# LCD_Cape.net
KiCad netlist of a schematic drawn in Altium Designer
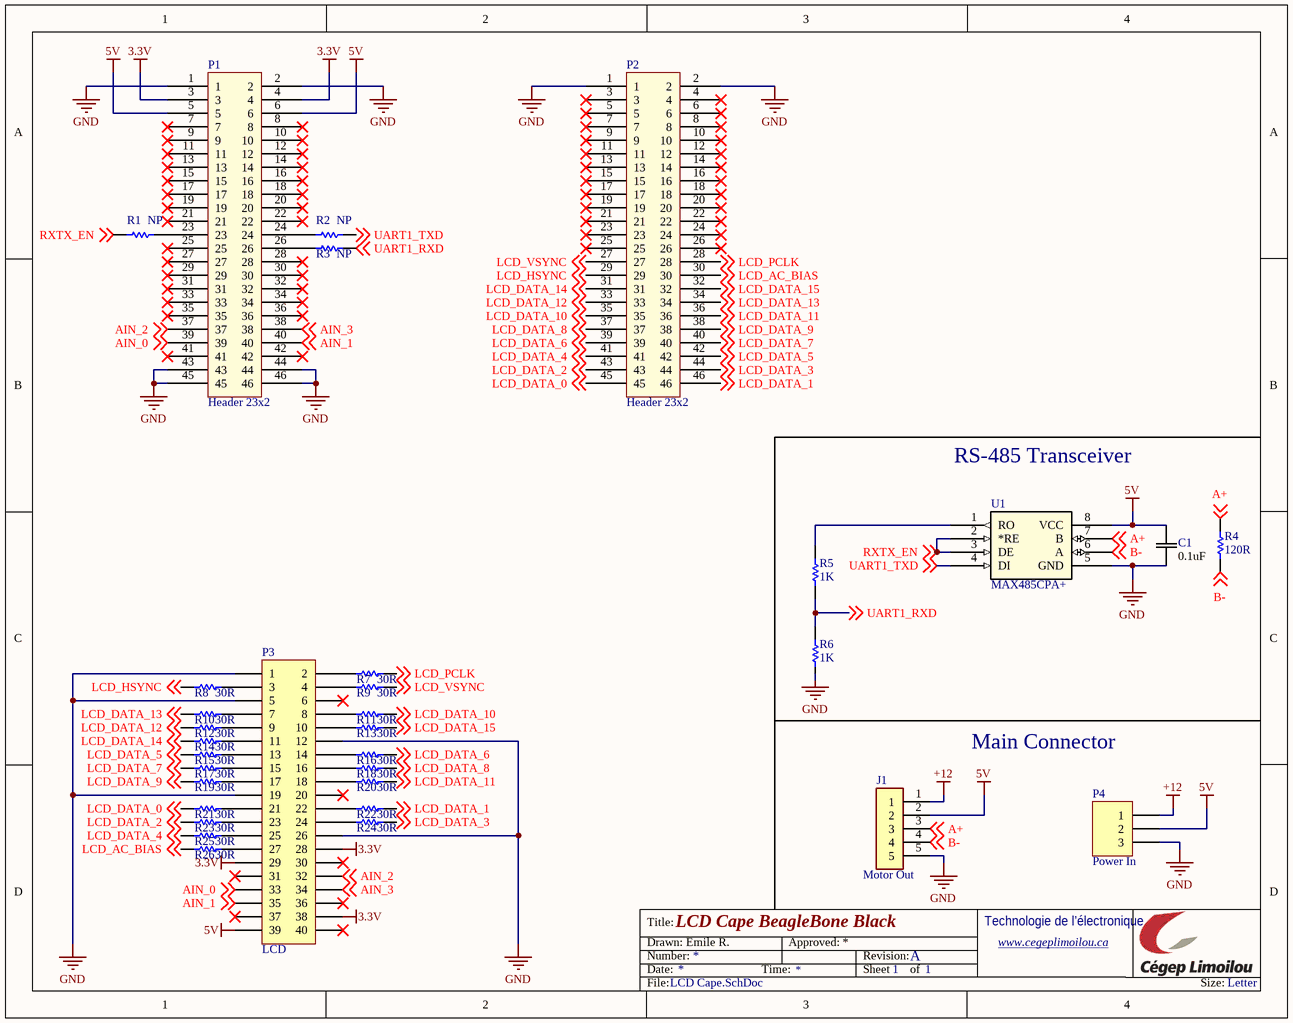
[diagram p0: LCD Cape.SchDoc]

(export (version "E")
  (design (tool "Eeschema 10.0.6"))
  (components
    (comp (ref "C1")
      (value "0.1uF")
      (footprint "0603")
      (description "Capacitor SMD 1206")
      (fields
        (field (name "MANUFACTURER_PART_NUMBER") "12065A820JAT2A")
        (field (name "Comment") "Capacitor 1206")
        (field (name "COPYRIGHT") "Copyright (C) 2018 Accelerated Designs. All rights reserved")
      )
      (libsource (lib "Schematic_Emile") (part "Capacitor 1206"))
    )
    (comp (ref "J1")
      (value "Motor Out")
      (footprint "JST 5POS 2.5mm 90°")
      (description "Connector")
      (fields (field (name "MANUFACTURER_PART_NUMBER") "S5B-XH-A-1(LF)(SN)"))
      (libsource (lib "Schematic_Emile") (part "JST 5POS"))
    )
    (comp (ref "P1")
      (value "Header 23x2")
      (footprint "Header 23x2")
      (libsource (lib "Schematic_Emile") (part "Header 23x2"))
    )
    (comp (ref "P2")
      (value "Header 23x2")
      (footprint "Header 23x2")
      (libsource (lib "Schematic_Emile") (part "Header 23x2"))
    )
    (comp (ref "P3")
      (value "LCD")
      (footprint "HDR2X20")
      (description "Header, 20-Pin, Dual row")
      (fields (field (name "PUBLISHER") "Altium Limited"))
      (libsource (lib "Miscellaneous Connectors") (part "Header 20X2"))
    )
    (comp (ref "P4")
      (value "Power In")
      (footprint "HDR1X3")
      (description "Header, 3-Pin")
      (fields (field (name "PUBLISHER") "Altium Limited"))
      (libsource (lib "Miscellaneous Connectors") (part "Header 3"))
    )
    (comp (ref "R1")
      (value "NP")
      (footprint "C1206")
      (description "Resistor")
      (fields (field (name "Comment") "Res1") (field (name "PUBLISHER") "Altium Limited"))
      (libsource (lib "Miscellaneous Devices") (part "Res1"))
    )
    (comp (ref "R2")
      (value "NP")
      (footprint "C1206")
      (description "Resistor")
      (fields (field (name "Comment") "Res1") (field (name "PUBLISHER") "Altium Limited"))
      (libsource (lib "Miscellaneous Devices") (part "Res1"))
    )
    (comp (ref "R3")
      (value "NP")
      (footprint "C1206")
      (description "Resistor")
      (fields (field (name "Comment") "Res1") (field (name "PUBLISHER") "Altium Limited"))
      (libsource (lib "Miscellaneous Devices") (part "Res1"))
    )
    (comp (ref "R4")
      (value "120R")
      (footprint "C1206")
      (description "Resistor")
      (fields (field (name "Comment") "Res1") (field (name "PUBLISHER") "Altium Limited"))
      (libsource (lib "Miscellaneous Devices") (part "Res1"))
    )
    (comp (ref "R5")
      (value "1K")
      (footprint "C1206")
      (description "Resistor")
      (fields (field (name "Comment") "Res1") (field (name "PUBLISHER") "Altium Limited"))
      (libsource (lib "Miscellaneous Devices") (part "Res1"))
    )
    (comp (ref "R6")
      (value "1K")
      (footprint "C1206")
      (description "Resistor")
      (fields (field (name "Comment") "Res1") (field (name "PUBLISHER") "Altium Limited"))
      (libsource (lib "Miscellaneous Devices") (part "Res1"))
    )
    (comp (ref "R7")
      (value "30R")
      (footprint "C1206")
      (description "Resistor")
      (fields (field (name "Comment") "Res1") (field (name "PUBLISHER") "Altium Limited"))
      (libsource (lib "Miscellaneous Devices") (part "Res1"))
    )
    (comp (ref "R8")
      (value "30R")
      (footprint "C1206")
      (description "Resistor")
      (fields (field (name "Comment") "Res1") (field (name "PUBLISHER") "Altium Limited"))
      (libsource (lib "Miscellaneous Devices") (part "Res1"))
    )
    (comp (ref "R9")
      (value "30R")
      (footprint "C1206")
      (description "Resistor")
      (fields (field (name "Comment") "Res1") (field (name "PUBLISHER") "Altium Limited"))
      (libsource (lib "Miscellaneous Devices") (part "Res1"))
    )
    (comp (ref "R10")
      (value "30R")
      (footprint "C1206")
      (description "Resistor")
      (fields (field (name "Comment") "Res1") (field (name "PUBLISHER") "Altium Limited"))
      (libsource (lib "Miscellaneous Devices") (part "Res1"))
    )
    (comp (ref "R11")
      (value "30R")
      (footprint "C1206")
      (description "Resistor")
      (fields (field (name "Comment") "Res1") (field (name "PUBLISHER") "Altium Limited"))
      (libsource (lib "Miscellaneous Devices") (part "Res1"))
    )
    (comp (ref "R12")
      (value "30R")
      (footprint "C1206")
      (description "Resistor")
      (fields (field (name "Comment") "Res1") (field (name "PUBLISHER") "Altium Limited"))
      (libsource (lib "Miscellaneous Devices") (part "Res1"))
    )
    (comp (ref "R13")
      (value "30R")
      (footprint "C1206")
      (description "Resistor")
      (fields (field (name "Comment") "Res1") (field (name "PUBLISHER") "Altium Limited"))
      (libsource (lib "Miscellaneous Devices") (part "Res1"))
    )
    (comp (ref "R14")
      (value "30R")
      (footprint "C1206")
      (description "Resistor")
      (fields (field (name "Comment") "Res1") (field (name "PUBLISHER") "Altium Limited"))
      (libsource (lib "Miscellaneous Devices") (part "Res1"))
    )
    (comp (ref "R15")
      (value "30R")
      (footprint "C1206")
      (description "Resistor")
      (fields (field (name "Comment") "Res1") (field (name "PUBLISHER") "Altium Limited"))
      (libsource (lib "Miscellaneous Devices") (part "Res1"))
    )
    (comp (ref "R16")
      (value "30R")
      (footprint "C1206")
      (description "Resistor")
      (fields (field (name "Comment") "Res1") (field (name "PUBLISHER") "Altium Limited"))
      (libsource (lib "Miscellaneous Devices") (part "Res1"))
    )
    (comp (ref "R17")
      (value "30R")
      (footprint "C1206")
      (description "Resistor")
      (fields (field (name "Comment") "Res1") (field (name "PUBLISHER") "Altium Limited"))
      (libsource (lib "Miscellaneous Devices") (part "Res1"))
    )
    (comp (ref "R18")
      (value "30R")
      (footprint "C1206")
      (description "Resistor")
      (fields (field (name "Comment") "Res1") (field (name "PUBLISHER") "Altium Limited"))
      (libsource (lib "Miscellaneous Devices") (part "Res1"))
    )
    (comp (ref "R19")
      (value "30R")
      (footprint "C1206")
      (description "Resistor")
      (fields (field (name "Comment") "Res1") (field (name "PUBLISHER") "Altium Limited"))
      (libsource (lib "Miscellaneous Devices") (part "Res1"))
    )
    (comp (ref "R20")
      (value "30R")
      (footprint "C1206")
      (description "Resistor")
      (fields (field (name "Comment") "Res1") (field (name "PUBLISHER") "Altium Limited"))
      (libsource (lib "Miscellaneous Devices") (part "Res1"))
    )
    (comp (ref "R21")
      (value "30R")
      (footprint "C1206")
      (description "Resistor")
      (fields (field (name "Comment") "Res1") (field (name "PUBLISHER") "Altium Limited"))
      (libsource (lib "Miscellaneous Devices") (part "Res1"))
    )
    (comp (ref "R22")
      (value "30R")
      (footprint "C1206")
      (description "Resistor")
      (fields (field (name "Comment") "Res1") (field (name "PUBLISHER") "Altium Limited"))
      (libsource (lib "Miscellaneous Devices") (part "Res1"))
    )
    (comp (ref "R23")
      (value "30R")
      (footprint "C1206")
      (description "Resistor")
      (fields (field (name "Comment") "Res1") (field (name "PUBLISHER") "Altium Limited"))
      (libsource (lib "Miscellaneous Devices") (part "Res1"))
    )
    (comp (ref "R24")
      (value "30R")
      (footprint "C1206")
      (description "Resistor")
      (fields (field (name "Comment") "Res1") (field (name "PUBLISHER") "Altium Limited"))
      (libsource (lib "Miscellaneous Devices") (part "Res1"))
    )
    (comp (ref "R25")
      (value "30R")
      (footprint "C1206")
      (description "Resistor")
      (fields (field (name "Comment") "Res1") (field (name "PUBLISHER") "Altium Limited"))
      (libsource (lib "Miscellaneous Devices") (part "Res1"))
    )
    (comp (ref "R26")
      (value "30R")
      (footprint "C1206")
      (description "Resistor")
      (fields (field (name "Comment") "Res1") (field (name "PUBLISHER") "Altium Limited"))
      (libsource (lib "Miscellaneous Devices") (part "Res1"))
    )
    (comp (ref "U1")
      (value "MAX485CPA+")
      (footprint "DIP 8 - 3D")
      (description "RS485 Communication")
      (fields (field (name "COPYRIGHT") "Copyright (C) 2018 Accelerated Designs. All rights reserved"))
      (libsource (lib "Schematic_Emile") (part "MAX485CPA+"))
    )
  )
  (nets
    (net (code "1") (name "+12") (class "Default")
      (node (ref "J1") (pin "1") (pinfunction "1_1") (pintype "passive"))
      (node (ref "P4") (pin "1") (pinfunction "1_1") (pintype "passive"))
    )
    (net (code "2") (name "3.3V") (class "Default")
      (node (ref "P1") (pin "3") (pinfunction "3_3") (pintype "passive"))
      (node (ref "P1") (pin "4") (pinfunction "4_4") (pintype "passive"))
      (node (ref "P3") (pin "28") (pinfunction "28_28") (pintype "passive"))
      (node (ref "P3") (pin "29") (pinfunction "29_29") (pintype "passive"))
      (node (ref "P3") (pin "38") (pinfunction "38_38") (pintype "passive"))
    )
    (net (code "3") (name "5V") (class "Default")
      (node (ref "C1") (pin "2") (pinfunction "2_2") (pintype "passive"))
      (node (ref "J1") (pin "2") (pinfunction "2_2") (pintype "passive"))
      (node (ref "P1") (pin "5") (pinfunction "5_5") (pintype "passive"))
      (node (ref "P1") (pin "6") (pinfunction "6_6") (pintype "passive"))
      (node (ref "P3") (pin "39") (pinfunction "39_39") (pintype "passive"))
      (node (ref "P4") (pin "2") (pinfunction "2_2") (pintype "passive"))
      (node (ref "U1") (pin "8") (pinfunction "VCC_8") (pintype "power_in"))
    )
    (net (code "4") (name "A+") (class "Default")
      (node (ref "J1") (pin "3") (pinfunction "3_3") (pintype "passive"))
      (node (ref "R4") (pin "1") (pinfunction "1_1") (pintype "passive"))
      (node (ref "U1") (pin "7") (pinfunction "B_7") (pintype "bidirectional"))
    )
    (net (code "5") (name "AIN_0") (class "Default")
      (node (ref "P1") (pin "39") (pinfunction "39_39") (pintype "passive"))
      (node (ref "P3") (pin "33") (pinfunction "33_33") (pintype "passive"))
    )
    (net (code "6") (name "AIN_1") (class "Default")
      (node (ref "P1") (pin "40") (pinfunction "40_40") (pintype "passive"))
      (node (ref "P3") (pin "35") (pinfunction "35_35") (pintype "passive"))
    )
    (net (code "7") (name "AIN_2") (class "Default")
      (node (ref "P1") (pin "37") (pinfunction "37_37") (pintype "passive"))
      (node (ref "P3") (pin "32") (pinfunction "32_32") (pintype "passive"))
    )
    (net (code "8") (name "AIN_3") (class "Default")
      (node (ref "P1") (pin "38") (pinfunction "38_38") (pintype "passive"))
      (node (ref "P3") (pin "34") (pinfunction "34_34") (pintype "passive"))
    )
    (net (code "9") (name "B-") (class "Default")
      (node (ref "J1") (pin "4") (pinfunction "4_4") (pintype "passive"))
      (node (ref "R4") (pin "2") (pinfunction "2_2") (pintype "passive"))
      (node (ref "U1") (pin "6") (pinfunction "A_6") (pintype "bidirectional"))
    )
    (net (code "10") (name "GND") (class "Default")
      (node (ref "C1") (pin "1") (pinfunction "1_1") (pintype "passive"))
      (node (ref "J1") (pin "5") (pinfunction "5_5") (pintype "passive"))
      (node (ref "P1") (pin "1") (pinfunction "1_1") (pintype "passive"))
      (node (ref "P1") (pin "2") (pinfunction "2_2") (pintype "passive"))
      (node (ref "P1") (pin "43") (pinfunction "43_43") (pintype "passive"))
      (node (ref "P1") (pin "44") (pinfunction "44_44") (pintype "passive"))
      (node (ref "P1") (pin "45") (pinfunction "45_45") (pintype "passive"))
      (node (ref "P1") (pin "46") (pinfunction "46_46") (pintype "passive"))
      (node (ref "P2") (pin "1") (pinfunction "1_1") (pintype "passive"))
      (node (ref "P2") (pin "2") (pinfunction "2_2") (pintype "passive"))
      (node (ref "P3") (pin "1") (pinfunction "1_1") (pintype "passive"))
      (node (ref "P3") (pin "12") (pinfunction "12_12") (pintype "passive"))
      (node (ref "P3") (pin "19") (pinfunction "19_19") (pintype "passive"))
      (node (ref "P3") (pin "26") (pinfunction "26_26") (pintype "passive"))
      (node (ref "P3") (pin "5") (pinfunction "5_5") (pintype "passive"))
      (node (ref "P4") (pin "3") (pinfunction "3_3") (pintype "passive"))
      (node (ref "R6") (pin "2") (pinfunction "2_2") (pintype "passive"))
      (node (ref "U1") (pin "5") (pinfunction "GND_5") (pintype "power_in"))
    )
    (net (code "11") (name "LCD_AC_BIAS") (class "Default")
      (node (ref "P2") (pin "30") (pinfunction "30_30") (pintype "passive"))
      (node (ref "R26") (pin "1") (pinfunction "1_1") (pintype "passive"))
    )
    (net (code "12") (name "LCD_DATA_0") (class "Default")
      (node (ref "P2") (pin "45") (pinfunction "45_45") (pintype "passive"))
      (node (ref "R21") (pin "1") (pinfunction "1_1") (pintype "passive"))
    )
    (net (code "13") (name "LCD_DATA_1") (class "Default")
      (node (ref "P2") (pin "46") (pinfunction "46_46") (pintype "passive"))
      (node (ref "R22") (pin "2") (pinfunction "2_2") (pintype "passive"))
    )
    (net (code "14") (name "LCD_DATA_2") (class "Default")
      (node (ref "P2") (pin "43") (pinfunction "43_43") (pintype "passive"))
      (node (ref "R23") (pin "1") (pinfunction "1_1") (pintype "passive"))
    )
    (net (code "15") (name "LCD_DATA_3") (class "Default")
      (node (ref "P2") (pin "44") (pinfunction "44_44") (pintype "passive"))
      (node (ref "R24") (pin "2") (pinfunction "2_2") (pintype "passive"))
    )
    (net (code "16") (name "LCD_DATA_4") (class "Default")
      (node (ref "P2") (pin "41") (pinfunction "41_41") (pintype "passive"))
      (node (ref "R25") (pin "1") (pinfunction "1_1") (pintype "passive"))
    )
    (net (code "17") (name "LCD_DATA_5") (class "Default")
      (node (ref "P2") (pin "42") (pinfunction "42_42") (pintype "passive"))
      (node (ref "R15") (pin "1") (pinfunction "1_1") (pintype "passive"))
    )
    (net (code "18") (name "LCD_DATA_6") (class "Default")
      (node (ref "P2") (pin "39") (pinfunction "39_39") (pintype "passive"))
      (node (ref "R16") (pin "2") (pinfunction "2_2") (pintype "passive"))
    )
    (net (code "19") (name "LCD_DATA_7") (class "Default")
      (node (ref "P2") (pin "40") (pinfunction "40_40") (pintype "passive"))
      (node (ref "R17") (pin "1") (pinfunction "1_1") (pintype "passive"))
    )
    (net (code "20") (name "LCD_DATA_8") (class "Default")
      (node (ref "P2") (pin "37") (pinfunction "37_37") (pintype "passive"))
      (node (ref "R18") (pin "2") (pinfunction "2_2") (pintype "passive"))
    )
    (net (code "21") (name "LCD_DATA_9") (class "Default")
      (node (ref "P2") (pin "38") (pinfunction "38_38") (pintype "passive"))
      (node (ref "R19") (pin "1") (pinfunction "1_1") (pintype "passive"))
    )
    (net (code "22") (name "LCD_DATA_10") (class "Default")
      (node (ref "P2") (pin "35") (pinfunction "35_35") (pintype "passive"))
      (node (ref "R11") (pin "2") (pinfunction "2_2") (pintype "passive"))
    )
    (net (code "23") (name "LCD_DATA_11") (class "Default")
      (node (ref "P2") (pin "36") (pinfunction "36_36") (pintype "passive"))
      (node (ref "R20") (pin "2") (pinfunction "2_2") (pintype "passive"))
    )
    (net (code "24") (name "LCD_DATA_12") (class "Default")
      (node (ref "P2") (pin "33") (pinfunction "33_33") (pintype "passive"))
      (node (ref "R12") (pin "1") (pinfunction "1_1") (pintype "passive"))
    )
    (net (code "25") (name "LCD_DATA_13") (class "Default")
      (node (ref "P2") (pin "34") (pinfunction "34_34") (pintype "passive"))
      (node (ref "R10") (pin "1") (pinfunction "1_1") (pintype "passive"))
    )
    (net (code "26") (name "LCD_DATA_14") (class "Default")
      (node (ref "P2") (pin "31") (pinfunction "31_31") (pintype "passive"))
      (node (ref "R14") (pin "1") (pinfunction "1_1") (pintype "passive"))
    )
    (net (code "27") (name "LCD_DATA_15") (class "Default")
      (node (ref "P2") (pin "32") (pinfunction "32_32") (pintype "passive"))
      (node (ref "R13") (pin "2") (pinfunction "2_2") (pintype "passive"))
    )
    (net (code "28") (name "LCD_HSYNC") (class "Default")
      (node (ref "P2") (pin "29") (pinfunction "29_29") (pintype "passive"))
      (node (ref "R8") (pin "1") (pinfunction "1_1") (pintype "passive"))
    )
    (net (code "29") (name "LCD_PCLK") (class "Default")
      (node (ref "P2") (pin "28") (pinfunction "28_28") (pintype "passive"))
      (node (ref "R7") (pin "2") (pinfunction "2_2") (pintype "passive"))
    )
    (net (code "30") (name "LCD_VSYNC") (class "Default")
      (node (ref "P2") (pin "27") (pinfunction "27_27") (pintype "passive"))
      (node (ref "R9") (pin "2") (pinfunction "2_2") (pintype "passive"))
    )
    (net (code "31") (name "Net-(P1-Pad23)") (class "Default")
      (node (ref "P1") (pin "23") (pinfunction "23_23") (pintype "passive"))
      (node (ref "R1") (pin "2") (pinfunction "2_2") (pintype "passive"))
    )
    (net (code "32") (name "Net-(P1-Pad24)") (class "Default")
      (node (ref "P1") (pin "24") (pinfunction "24_24") (pintype "passive"))
      (node (ref "R2") (pin "1") (pinfunction "1_1") (pintype "passive"))
    )
    (net (code "33") (name "Net-(P1-Pad26)") (class "Default")
      (node (ref "P1") (pin "26") (pinfunction "26_26") (pintype "passive"))
      (node (ref "R3") (pin "1") (pinfunction "1_1") (pintype "passive"))
    )
    (net (code "34") (name "Net-(P3-Pad2)") (class "Default")
      (node (ref "P3") (pin "2") (pinfunction "2_2") (pintype "passive"))
      (node (ref "R7") (pin "1") (pinfunction "1_1") (pintype "passive"))
    )
    (net (code "35") (name "Net-(P3-Pad3)") (class "Default")
      (node (ref "P3") (pin "3") (pinfunction "3_3") (pintype "passive"))
      (node (ref "R8") (pin "2") (pinfunction "2_2") (pintype "passive"))
    )
    (net (code "36") (name "Net-(P3-Pad4)") (class "Default")
      (node (ref "P3") (pin "4") (pinfunction "4_4") (pintype "passive"))
      (node (ref "R9") (pin "1") (pinfunction "1_1") (pintype "passive"))
    )
    (net (code "37") (name "Net-(P3-Pad7)") (class "Default")
      (node (ref "P3") (pin "7") (pinfunction "7_7") (pintype "passive"))
      (node (ref "R10") (pin "2") (pinfunction "2_2") (pintype "passive"))
    )
    (net (code "38") (name "Net-(P3-Pad8)") (class "Default")
      (node (ref "P3") (pin "8") (pinfunction "8_8") (pintype "passive"))
      (node (ref "R11") (pin "1") (pinfunction "1_1") (pintype "passive"))
    )
    (net (code "39") (name "Net-(P3-Pad9)") (class "Default")
      (node (ref "P3") (pin "9") (pinfunction "9_9") (pintype "passive"))
      (node (ref "R12") (pin "2") (pinfunction "2_2") (pintype "passive"))
    )
    (net (code "40") (name "Net-(P3-Pad10)") (class "Default")
      (node (ref "P3") (pin "10") (pinfunction "10_10") (pintype "passive"))
      (node (ref "R13") (pin "1") (pinfunction "1_1") (pintype "passive"))
    )
    (net (code "41") (name "Net-(P3-Pad11)") (class "Default")
      (node (ref "P3") (pin "11") (pinfunction "11_11") (pintype "passive"))
      (node (ref "R14") (pin "2") (pinfunction "2_2") (pintype "passive"))
    )
    (net (code "42") (name "Net-(P3-Pad13)") (class "Default")
      (node (ref "P3") (pin "13") (pinfunction "13_13") (pintype "passive"))
      (node (ref "R15") (pin "2") (pinfunction "2_2") (pintype "passive"))
    )
    (net (code "43") (name "Net-(P3-Pad14)") (class "Default")
      (node (ref "P3") (pin "14") (pinfunction "14_14") (pintype "passive"))
      (node (ref "R16") (pin "1") (pinfunction "1_1") (pintype "passive"))
    )
    (net (code "44") (name "Net-(P3-Pad15)") (class "Default")
      (node (ref "P3") (pin "15") (pinfunction "15_15") (pintype "passive"))
      (node (ref "R17") (pin "2") (pinfunction "2_2") (pintype "passive"))
    )
    (net (code "45") (name "Net-(P3-Pad16)") (class "Default")
      (node (ref "P3") (pin "16") (pinfunction "16_16") (pintype "passive"))
      (node (ref "R18") (pin "1") (pinfunction "1_1") (pintype "passive"))
    )
    (net (code "46") (name "Net-(P3-Pad17)") (class "Default")
      (node (ref "P3") (pin "17") (pinfunction "17_17") (pintype "passive"))
      (node (ref "R19") (pin "2") (pinfunction "2_2") (pintype "passive"))
    )
    (net (code "47") (name "Net-(P3-Pad18)") (class "Default")
      (node (ref "P3") (pin "18") (pinfunction "18_18") (pintype "passive"))
      (node (ref "R20") (pin "1") (pinfunction "1_1") (pintype "passive"))
    )
    (net (code "48") (name "Net-(P3-Pad21)") (class "Default")
      (node (ref "P3") (pin "21") (pinfunction "21_21") (pintype "passive"))
      (node (ref "R21") (pin "2") (pinfunction "2_2") (pintype "passive"))
    )
    (net (code "49") (name "Net-(P3-Pad22)") (class "Default")
      (node (ref "P3") (pin "22") (pinfunction "22_22") (pintype "passive"))
      (node (ref "R22") (pin "1") (pinfunction "1_1") (pintype "passive"))
    )
    (net (code "50") (name "Net-(P3-Pad23)") (class "Default")
      (node (ref "P3") (pin "23") (pinfunction "23_23") (pintype "passive"))
      (node (ref "R23") (pin "2") (pinfunction "2_2") (pintype "passive"))
    )
    (net (code "51") (name "Net-(P3-Pad24)") (class "Default")
      (node (ref "P3") (pin "24") (pinfunction "24_24") (pintype "passive"))
      (node (ref "R24") (pin "1") (pinfunction "1_1") (pintype "passive"))
    )
    (net (code "52") (name "Net-(P3-Pad25)") (class "Default")
      (node (ref "P3") (pin "25") (pinfunction "25_25") (pintype "passive"))
      (node (ref "R25") (pin "2") (pinfunction "2_2") (pintype "passive"))
    )
    (net (code "53") (name "Net-(P3-Pad27)") (class "Default")
      (node (ref "P3") (pin "27") (pinfunction "27_27") (pintype "passive"))
      (node (ref "R26") (pin "2") (pinfunction "2_2") (pintype "passive"))
    )
    (net (code "54") (name "Net-(U1-RO)") (class "Default")
      (node (ref "R5") (pin "1") (pinfunction "1_1") (pintype "passive"))
      (node (ref "U1") (pin "1") (pinfunction "RO_1") (pintype "output"))
    )
    (net (code "55") (name "RXTX_EN") (class "Default")
      (node (ref "R1") (pin "1") (pinfunction "1_1") (pintype "passive"))
      (node (ref "U1") (pin "2") (pinfunction "*RE_2") (pintype "input"))
      (node (ref "U1") (pin "3") (pinfunction "DE_3") (pintype "input"))
    )
    (net (code "56") (name "UART1_RXD") (class "Default")
      (node (ref "R3") (pin "2") (pinfunction "2_2") (pintype "passive"))
      (node (ref "R5") (pin "2") (pinfunction "2_2") (pintype "passive"))
      (node (ref "R6") (pin "1") (pinfunction "1_1") (pintype "passive"))
    )
    (net (code "57") (name "UART1_TXD") (class "Default")
      (node (ref "R2") (pin "2") (pinfunction "2_2") (pintype "passive"))
      (node (ref "U1") (pin "4") (pinfunction "DI_4") (pintype "input"))
    )
    (net (code "58") (name "unconnected-(P1-Pad7)") (class "Default")
      (node (ref "P1") (pin "7") (pinfunction "7_7") (pintype "passive+no_connect"))
    )
    (net (code "59") (name "unconnected-(P1-Pad8)") (class "Default")
      (node (ref "P1") (pin "8") (pinfunction "8_8") (pintype "passive+no_connect"))
    )
    (net (code "60") (name "unconnected-(P1-Pad9)") (class "Default")
      (node (ref "P1") (pin "9") (pinfunction "9_9") (pintype "passive+no_connect"))
    )
    (net (code "61") (name "unconnected-(P1-Pad10)") (class "Default")
      (node (ref "P1") (pin "10") (pinfunction "10_10") (pintype "passive+no_connect"))
    )
    (net (code "62") (name "unconnected-(P1-Pad11)") (class "Default")
      (node (ref "P1") (pin "11") (pinfunction "11_11") (pintype "passive+no_connect"))
    )
    (net (code "63") (name "unconnected-(P1-Pad12)") (class "Default")
      (node (ref "P1") (pin "12") (pinfunction "12_12") (pintype "passive+no_connect"))
    )
    (net (code "64") (name "unconnected-(P1-Pad13)") (class "Default")
      (node (ref "P1") (pin "13") (pinfunction "13_13") (pintype "passive+no_connect"))
    )
    (net (code "65") (name "unconnected-(P1-Pad14)") (class "Default")
      (node (ref "P1") (pin "14") (pinfunction "14_14") (pintype "passive+no_connect"))
    )
    (net (code "66") (name "unconnected-(P1-Pad15)") (class "Default")
      (node (ref "P1") (pin "15") (pinfunction "15_15") (pintype "passive+no_connect"))
    )
    (net (code "67") (name "unconnected-(P1-Pad16)") (class "Default")
      (node (ref "P1") (pin "16") (pinfunction "16_16") (pintype "passive+no_connect"))
    )
    (net (code "68") (name "unconnected-(P1-Pad17)") (class "Default")
      (node (ref "P1") (pin "17") (pinfunction "17_17") (pintype "passive+no_connect"))
    )
    (net (code "69") (name "unconnected-(P1-Pad18)") (class "Default")
      (node (ref "P1") (pin "18") (pinfunction "18_18") (pintype "passive+no_connect"))
    )
    (net (code "70") (name "unconnected-(P1-Pad19)") (class "Default")
      (node (ref "P1") (pin "19") (pinfunction "19_19") (pintype "passive+no_connect"))
    )
    (net (code "71") (name "unconnected-(P1-Pad20)") (class "Default")
      (node (ref "P1") (pin "20") (pinfunction "20_20") (pintype "passive+no_connect"))
    )
    (net (code "72") (name "unconnected-(P1-Pad21)") (class "Default")
      (node (ref "P1") (pin "21") (pinfunction "21_21") (pintype "passive+no_connect"))
    )
    (net (code "73") (name "unconnected-(P1-Pad22)") (class "Default")
      (node (ref "P1") (pin "22") (pinfunction "22_22") (pintype "passive+no_connect"))
    )
    (net (code "74") (name "unconnected-(P1-Pad25)") (class "Default")
      (node (ref "P1") (pin "25") (pinfunction "25_25") (pintype "passive+no_connect"))
    )
    (net (code "75") (name "unconnected-(P1-Pad27)") (class "Default")
      (node (ref "P1") (pin "27") (pinfunction "27_27") (pintype "passive+no_connect"))
    )
    (net (code "76") (name "unconnected-(P1-Pad28)") (class "Default")
      (node (ref "P1") (pin "28") (pinfunction "28_28") (pintype "passive+no_connect"))
    )
    (net (code "77") (name "unconnected-(P1-Pad29)") (class "Default")
      (node (ref "P1") (pin "29") (pinfunction "29_29") (pintype "passive+no_connect"))
    )
    (net (code "78") (name "unconnected-(P1-Pad30)") (class "Default")
      (node (ref "P1") (pin "30") (pinfunction "30_30") (pintype "passive+no_connect"))
    )
    (net (code "79") (name "unconnected-(P1-Pad31)") (class "Default")
      (node (ref "P1") (pin "31") (pinfunction "31_31") (pintype "passive+no_connect"))
    )
    (net (code "80") (name "unconnected-(P1-Pad32)") (class "Default")
      (node (ref "P1") (pin "32") (pinfunction "32_32") (pintype "passive+no_connect"))
    )
    (net (code "81") (name "unconnected-(P1-Pad33)") (class "Default")
      (node (ref "P1") (pin "33") (pinfunction "33_33") (pintype "passive+no_connect"))
    )
    (net (code "82") (name "unconnected-(P1-Pad34)") (class "Default")
      (node (ref "P1") (pin "34") (pinfunction "34_34") (pintype "passive+no_connect"))
    )
    (net (code "83") (name "unconnected-(P1-Pad35)") (class "Default")
      (node (ref "P1") (pin "35") (pinfunction "35_35") (pintype "passive+no_connect"))
    )
    (net (code "84") (name "unconnected-(P1-Pad36)") (class "Default")
      (node (ref "P1") (pin "36") (pinfunction "36_36") (pintype "passive+no_connect"))
    )
    (net (code "85") (name "unconnected-(P1-Pad41)") (class "Default")
      (node (ref "P1") (pin "41") (pinfunction "41_41") (pintype "passive+no_connect"))
    )
    (net (code "86") (name "unconnected-(P1-Pad42)") (class "Default")
      (node (ref "P1") (pin "42") (pinfunction "42_42") (pintype "passive+no_connect"))
    )
    (net (code "87") (name "unconnected-(P2-Pad3)") (class "Default")
      (node (ref "P2") (pin "3") (pinfunction "3_3") (pintype "passive+no_connect"))
    )
    (net (code "88") (name "unconnected-(P2-Pad4)") (class "Default")
      (node (ref "P2") (pin "4") (pinfunction "4_4") (pintype "passive+no_connect"))
    )
    (net (code "89") (name "unconnected-(P2-Pad5)") (class "Default")
      (node (ref "P2") (pin "5") (pinfunction "5_5") (pintype "passive+no_connect"))
    )
    (net (code "90") (name "unconnected-(P2-Pad6)") (class "Default")
      (node (ref "P2") (pin "6") (pinfunction "6_6") (pintype "passive+no_connect"))
    )
    (net (code "91") (name "unconnected-(P2-Pad7)") (class "Default")
      (node (ref "P2") (pin "7") (pinfunction "7_7") (pintype "passive+no_connect"))
    )
    (net (code "92") (name "unconnected-(P2-Pad8)") (class "Default")
      (node (ref "P2") (pin "8") (pinfunction "8_8") (pintype "passive+no_connect"))
    )
    (net (code "93") (name "unconnected-(P2-Pad9)") (class "Default")
      (node (ref "P2") (pin "9") (pinfunction "9_9") (pintype "passive+no_connect"))
    )
    (net (code "94") (name "unconnected-(P2-Pad10)") (class "Default")
      (node (ref "P2") (pin "10") (pinfunction "10_10") (pintype "passive+no_connect"))
    )
    (net (code "95") (name "unconnected-(P2-Pad11)") (class "Default")
      (node (ref "P2") (pin "11") (pinfunction "11_11") (pintype "passive+no_connect"))
    )
    (net (code "96") (name "unconnected-(P2-Pad12)") (class "Default")
      (node (ref "P2") (pin "12") (pinfunction "12_12") (pintype "passive+no_connect"))
    )
    (net (code "97") (name "unconnected-(P2-Pad13)") (class "Default")
      (node (ref "P2") (pin "13") (pinfunction "13_13") (pintype "passive+no_connect"))
    )
    (net (code "98") (name "unconnected-(P2-Pad14)") (class "Default")
      (node (ref "P2") (pin "14") (pinfunction "14_14") (pintype "passive+no_connect"))
    )
    (net (code "99") (name "unconnected-(P2-Pad15)") (class "Default")
      (node (ref "P2") (pin "15") (pinfunction "15_15") (pintype "passive+no_connect"))
    )
    (net (code "100") (name "unconnected-(P2-Pad16)") (class "Default")
      (node (ref "P2") (pin "16") (pinfunction "16_16") (pintype "passive+no_connect"))
    )
    (net (code "101") (name "unconnected-(P2-Pad17)") (class "Default")
      (node (ref "P2") (pin "17") (pinfunction "17_17") (pintype "passive+no_connect"))
    )
    (net (code "102") (name "unconnected-(P2-Pad18)") (class "Default")
      (node (ref "P2") (pin "18") (pinfunction "18_18") (pintype "passive+no_connect"))
    )
    (net (code "103") (name "unconnected-(P2-Pad19)") (class "Default")
      (node (ref "P2") (pin "19") (pinfunction "19_19") (pintype "passive+no_connect"))
    )
    (net (code "104") (name "unconnected-(P2-Pad20)") (class "Default")
      (node (ref "P2") (pin "20") (pinfunction "20_20") (pintype "passive+no_connect"))
    )
    (net (code "105") (name "unconnected-(P2-Pad21)") (class "Default")
      (node (ref "P2") (pin "21") (pinfunction "21_21") (pintype "passive+no_connect"))
    )
    (net (code "106") (name "unconnected-(P2-Pad22)") (class "Default")
      (node (ref "P2") (pin "22") (pinfunction "22_22") (pintype "passive+no_connect"))
    )
    (net (code "107") (name "unconnected-(P2-Pad23)") (class "Default")
      (node (ref "P2") (pin "23") (pinfunction "23_23") (pintype "passive+no_connect"))
    )
    (net (code "108") (name "unconnected-(P2-Pad24)") (class "Default")
      (node (ref "P2") (pin "24") (pinfunction "24_24") (pintype "passive+no_connect"))
    )
    (net (code "109") (name "unconnected-(P2-Pad25)") (class "Default")
      (node (ref "P2") (pin "25") (pinfunction "25_25") (pintype "passive+no_connect"))
    )
    (net (code "110") (name "unconnected-(P2-Pad26)") (class "Default")
      (node (ref "P2") (pin "26") (pinfunction "26_26") (pintype "passive+no_connect"))
    )
    (net (code "111") (name "unconnected-(P3-Pad6)") (class "Default")
      (node (ref "P3") (pin "6") (pinfunction "6_6") (pintype "passive+no_connect"))
    )
    (net (code "112") (name "unconnected-(P3-Pad20)") (class "Default")
      (node (ref "P3") (pin "20") (pinfunction "20_20") (pintype "passive+no_connect"))
    )
    (net (code "113") (name "unconnected-(P3-Pad30)") (class "Default")
      (node (ref "P3") (pin "30") (pinfunction "30_30") (pintype "passive+no_connect"))
    )
    (net (code "114") (name "unconnected-(P3-Pad31)") (class "Default")
      (node (ref "P3") (pin "31") (pinfunction "31_31") (pintype "passive+no_connect"))
    )
    (net (code "115") (name "unconnected-(P3-Pad36)") (class "Default")
      (node (ref "P3") (pin "36") (pinfunction "36_36") (pintype "passive+no_connect"))
    )
    (net (code "116") (name "unconnected-(P3-Pad37)") (class "Default")
      (node (ref "P3") (pin "37") (pinfunction "37_37") (pintype "passive+no_connect"))
    )
    (net (code "117") (name "unconnected-(P3-Pad40)") (class "Default")
      (node (ref "P3") (pin "40") (pinfunction "40_40") (pintype "passive+no_connect"))
    )
  )
)
